# Schematic_v1.net
KiCad netlist of a schematic drawn in EAGLE
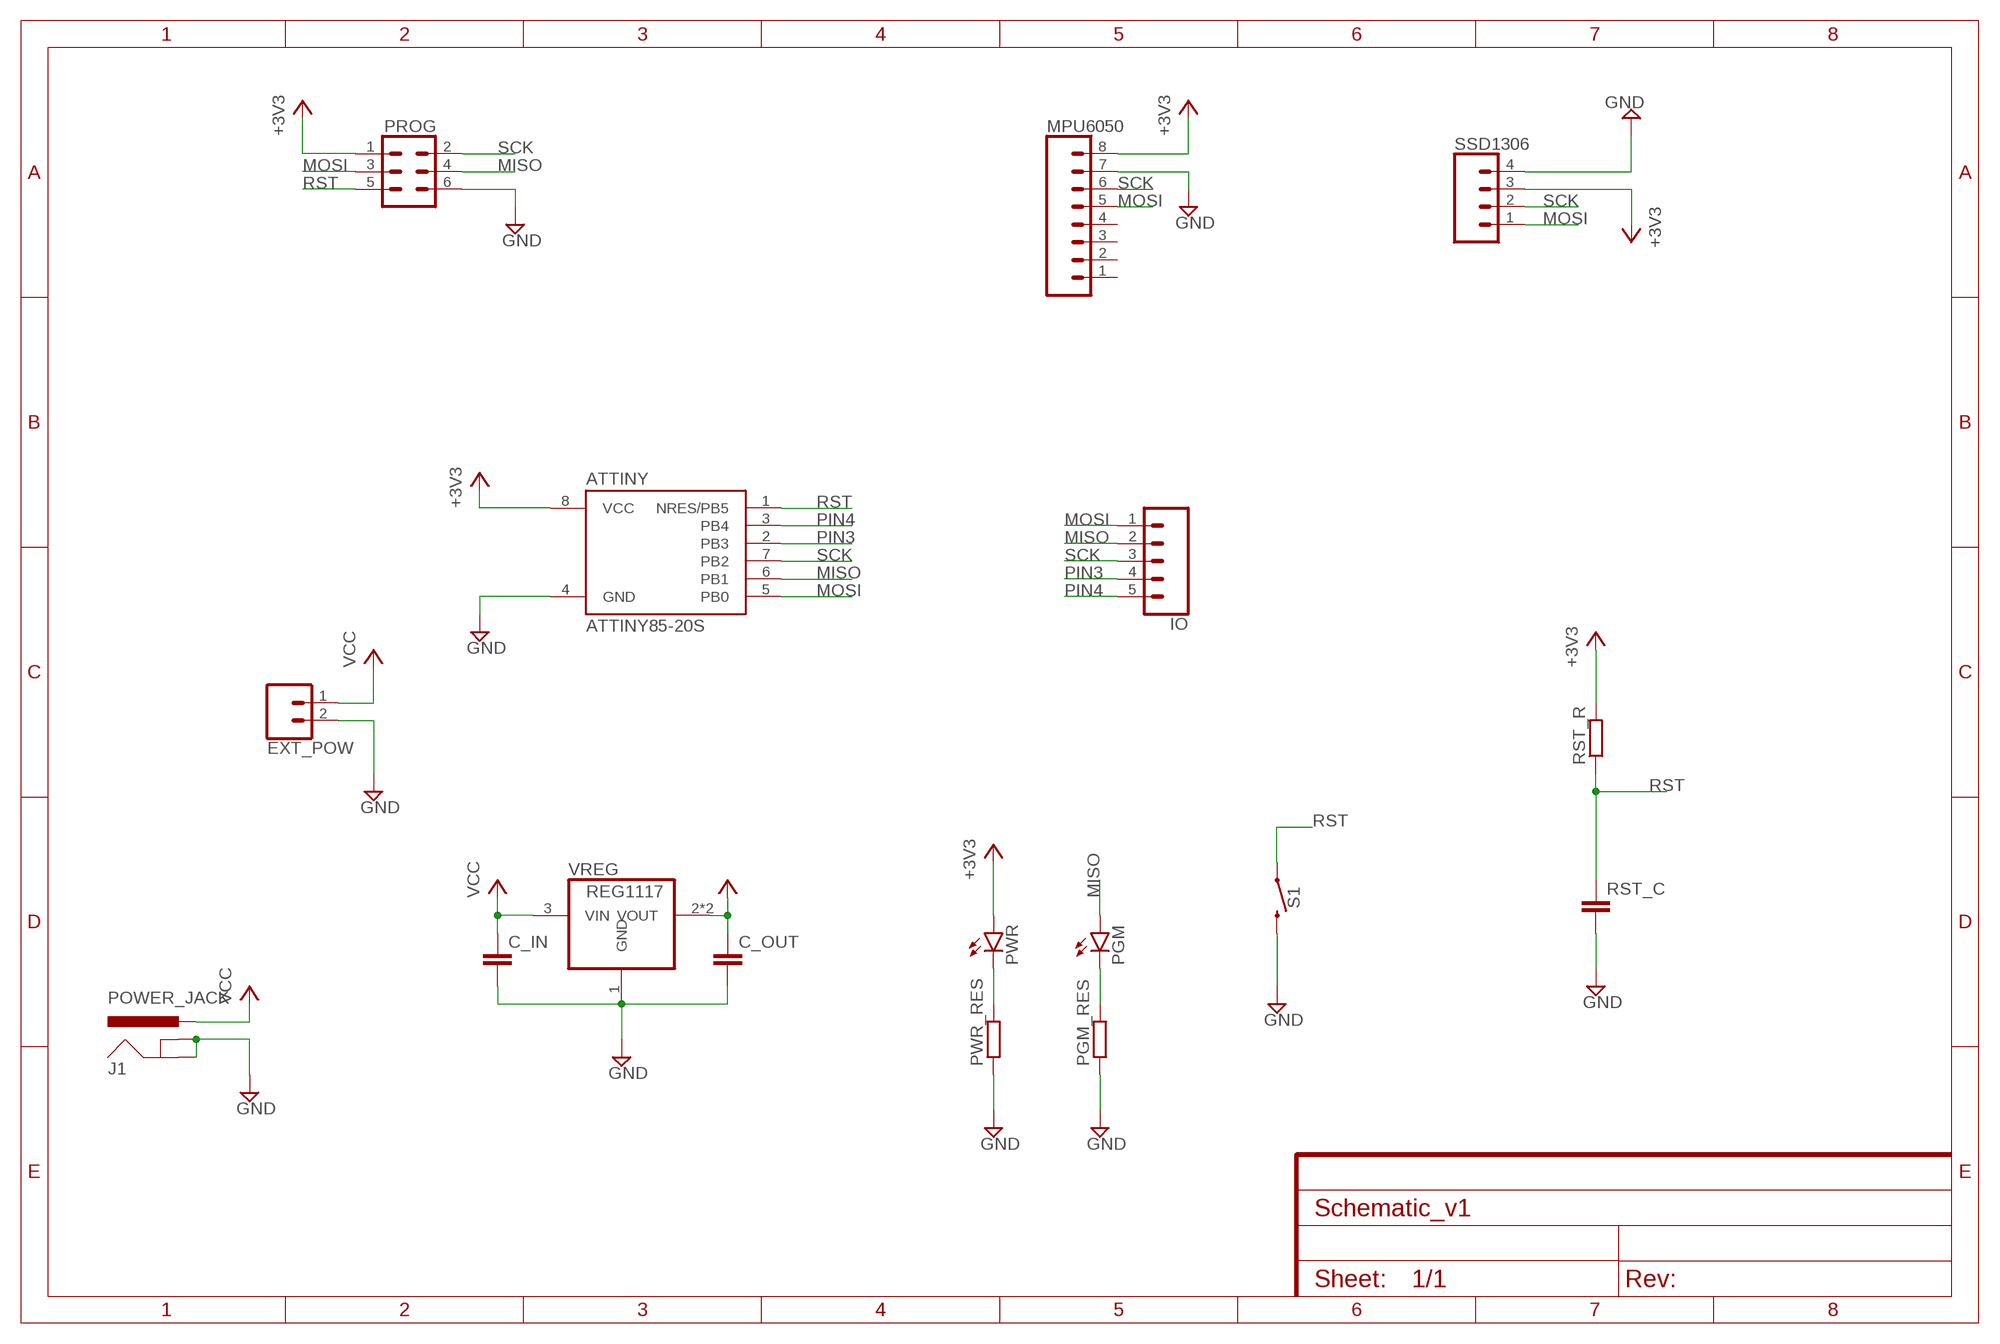
[diagram p0: schematic, sheet 1]

(export (version "E")
  (design (tool "Eeschema 10.0.6"))
  (components
    (comp (ref "ATTINY")
      (value "ATTINY85-20S")
      (footprint "eagle-import:SOIC8_EIAJ_208MIL")
      (libsource (lib "eagle-import") (part "ATTINY85S-20"))
    )
    (comp (ref "C_IN")
      (value "C-EUC1206")
      (footprint "eagle-import:C1206")
      (libsource (lib "eagle-import") (part "C-EUC1206"))
    )
    (comp (ref "C_OUT")
      (value "C-EUC1206")
      (footprint "eagle-import:C1206")
      (libsource (lib "eagle-import") (part "C-EUC1206"))
    )
    (comp (ref "EXT_POW")
      (value "CONN_021X02_NO_SILK")
      (footprint "eagle-import:1X02_NO_SILK")
      (libsource (lib "eagle-import") (part "CONN_021X02_NO_SILK"))
    )
    (comp (ref "IO")
      (value "CONN_05")
      (footprint "eagle-import:1X05")
      (libsource (lib "eagle-import") (part "CONN_05"))
    )
    (comp (ref "J1")
      (value "POWER_JACK")
      (footprint "eagle-import:POWER_JACK_PTH")
      (libsource (lib "eagle-import") (part "POWER_JACK"))
    )
    (comp (ref "MPU6050")
      (value "CONN_08\"")
      (footprint "eagle-import:1X08")
      (libsource (lib "eagle-import") (part "CONN_08{dblquote}"))
    )
    (comp (ref "PGM")
      (value "LEDSML1206")
      (footprint "eagle-import:SML1206")
      (libsource (lib "eagle-import") (part "LEDSML1206"))
    )
    (comp (ref "PGM_RES")
      (value "R-EU_R1206")
      (footprint "eagle-import:R1206")
      (libsource (lib "eagle-import") (part "R-EU_R1206"))
    )
    (comp (ref "PROG")
      (value "CONN_03X2NO_SILK")
      (footprint "eagle-import:2X3-NS")
      (libsource (lib "eagle-import") (part "CONN_03X2NO_SILK"))
    )
    (comp (ref "PWR")
      (value "LEDSML1206")
      (footprint "eagle-import:SML1206")
      (libsource (lib "eagle-import") (part "LEDSML1206"))
    )
    (comp (ref "PWR_RES")
      (value "R-EU_R1206")
      (footprint "eagle-import:R1206")
      (libsource (lib "eagle-import") (part "R-EU_R1206"))
    )
    (comp (ref "RST_C")
      (value "C-EUC1206")
      (footprint "eagle-import:C1206")
      (libsource (lib "eagle-import") (part "C-EUC1206"))
    )
    (comp (ref "RST_R")
      (value "R-EU_R1206")
      (footprint "eagle-import:R1206")
      (libsource (lib "eagle-import") (part "R-EU_R1206"))
    )
    (comp (ref "S1")
      (value "MOMENTARY-SWITCH-SPST-PTH-6.0MM")
      (footprint "eagle-import:TACTILE_SWITCH_PTH_6.0MM")
      (libsource (lib "eagle-import") (part "MOMENTARY-SWITCH-SPST-PTH-6.0MM"))
    )
    (comp (ref "SSD1306")
      (value "CONN_04")
      (footprint "eagle-import:1X04")
      (libsource (lib "eagle-import") (part "CONN_04"))
    )
    (comp (ref "VREG")
      (value "REG1117")
      (footprint "eagle-import:SOT223")
      (libsource (lib "eagle-import") (part "REG1117"))
    )
  )
  (nets
    (net (code "1") (name "+3V3") (class "Default")
      (node (ref "ATTINY") (pin "8") (pinfunction "VCC_8") (pintype "power_in"))
      (node (ref "C_OUT") (pin "1") (pinfunction "1_1") (pintype "passive"))
      (node (ref "MPU6050") (pin "8") (pinfunction "8_8") (pintype "passive"))
      (node (ref "PROG") (pin "1") (pinfunction "1_1") (pintype "bidirectional"))
      (node (ref "PWR") (pin "A") (pinfunction "A_A") (pintype "passive"))
      (node (ref "RST_R") (pin "2") (pinfunction "2_2") (pintype "passive"))
      (node (ref "SSD1306") (pin "3") (pinfunction "3_3") (pintype "passive"))
      (node (ref "VREG") (pin "2") (pinfunction "VOUT_2") (pintype "output"))
      (node (ref "VREG") (pin "4") (pinfunction "VOUT_4") (pintype "output"))
    )
    (net (code "2") (name "/MISO") (class "Default")
      (node (ref "ATTINY") (pin "6") (pinfunction "PB1_6") (pintype "bidirectional"))
      (node (ref "IO") (pin "2") (pinfunction "2_2") (pintype "passive"))
      (node (ref "PGM") (pin "A") (pinfunction "A_A") (pintype "passive"))
      (node (ref "PROG") (pin "4") (pinfunction "4_4") (pintype "bidirectional"))
    )
    (net (code "3") (name "/MOSI") (class "Default")
      (node (ref "ATTINY") (pin "5") (pinfunction "PB0_5") (pintype "bidirectional"))
      (node (ref "IO") (pin "1") (pinfunction "1_1") (pintype "passive"))
      (node (ref "MPU6050") (pin "5") (pinfunction "5_5") (pintype "passive"))
      (node (ref "PROG") (pin "3") (pinfunction "3_3") (pintype "bidirectional"))
      (node (ref "SSD1306") (pin "1") (pinfunction "1_1") (pintype "passive"))
    )
    (net (code "4") (name "/PIN3") (class "Default")
      (node (ref "ATTINY") (pin "2") (pinfunction "PB3_2") (pintype "bidirectional"))
      (node (ref "IO") (pin "4") (pinfunction "4_4") (pintype "passive"))
    )
    (net (code "5") (name "/PIN4") (class "Default")
      (node (ref "ATTINY") (pin "3") (pinfunction "PB4_3") (pintype "bidirectional"))
      (node (ref "IO") (pin "5") (pinfunction "5_5") (pintype "passive"))
    )
    (net (code "6") (name "/RST") (class "Default")
      (node (ref "ATTINY") (pin "1") (pinfunction "NRES/PB5_1") (pintype "bidirectional"))
      (node (ref "PROG") (pin "5") (pinfunction "5_5") (pintype "bidirectional"))
      (node (ref "RST_C") (pin "1") (pinfunction "1_1") (pintype "passive"))
      (node (ref "RST_R") (pin "1") (pinfunction "1_1") (pintype "passive"))
      (node (ref "S1") (pin "1") (pinfunction "1_1") (pintype "passive"))
    )
    (net (code "7") (name "/SCK") (class "Default")
      (node (ref "ATTINY") (pin "7") (pinfunction "PB2_7") (pintype "bidirectional"))
      (node (ref "IO") (pin "3") (pinfunction "3_3") (pintype "passive"))
      (node (ref "MPU6050") (pin "6") (pinfunction "6_6") (pintype "passive"))
      (node (ref "PROG") (pin "2") (pinfunction "2_2") (pintype "bidirectional"))
      (node (ref "SSD1306") (pin "2") (pinfunction "2_2") (pintype "passive"))
    )
    (net (code "8") (name "GND") (class "Default")
      (node (ref "ATTINY") (pin "4") (pinfunction "GND_4") (pintype "power_in"))
      (node (ref "C_IN") (pin "2") (pinfunction "2_2") (pintype "passive"))
      (node (ref "C_OUT") (pin "2") (pinfunction "2_2") (pintype "passive"))
      (node (ref "EXT_POW") (pin "2") (pinfunction "2_2") (pintype "passive"))
      (node (ref "J1") (pin "GND") (pinfunction "GND_GND") (pintype "bidirectional"))
      (node (ref "J1") (pin "GNDBREAK") (pinfunction "GNDBREAK_GNDBREAK") (pintype "bidirectional"))
      (node (ref "MPU6050") (pin "7") (pinfunction "7_7") (pintype "passive"))
      (node (ref "PGM_RES") (pin "1") (pinfunction "1_1") (pintype "passive"))
      (node (ref "PROG") (pin "6") (pinfunction "6_6") (pintype "bidirectional"))
      (node (ref "PWR_RES") (pin "1") (pinfunction "1_1") (pintype "passive"))
      (node (ref "RST_C") (pin "2") (pinfunction "2_2") (pintype "passive"))
      (node (ref "S1") (pin "3") (pinfunction "2_3") (pintype "passive"))
      (node (ref "SSD1306") (pin "4") (pinfunction "4_4") (pintype "passive"))
      (node (ref "VREG") (pin "1") (pinfunction "GND_1") (pintype "power_in"))
    )
    (net (code "9") (name "Net-(PGM-PadC)") (class "Default")
      (node (ref "PGM") (pin "C") (pinfunction "C_C") (pintype "passive"))
      (node (ref "PGM_RES") (pin "2") (pinfunction "2_2") (pintype "passive"))
    )
    (net (code "10") (name "Net-(PWR-PadC)") (class "Default")
      (node (ref "PWR") (pin "C") (pinfunction "C_C") (pintype "passive"))
      (node (ref "PWR_RES") (pin "2") (pinfunction "2_2") (pintype "passive"))
    )
    (net (code "11") (name "VCC") (class "Default")
      (node (ref "C_IN") (pin "1") (pinfunction "1_1") (pintype "passive"))
      (node (ref "EXT_POW") (pin "1") (pinfunction "1_1") (pintype "passive"))
      (node (ref "J1") (pin "PWR") (pinfunction "PWR_PWR") (pintype "bidirectional"))
      (node (ref "VREG") (pin "3") (pinfunction "VIN_3") (pintype "input"))
    )
    (net (code "12") (name "unconnected-(MPU6050-Pad1)") (class "Default")
      (node (ref "MPU6050") (pin "1") (pinfunction "1_1") (pintype "passive"))
    )
    (net (code "13") (name "unconnected-(MPU6050-Pad2)") (class "Default")
      (node (ref "MPU6050") (pin "2") (pinfunction "2_2") (pintype "passive"))
    )
    (net (code "14") (name "unconnected-(MPU6050-Pad3)") (class "Default")
      (node (ref "MPU6050") (pin "3") (pinfunction "3_3") (pintype "passive"))
    )
    (net (code "15") (name "unconnected-(MPU6050-Pad4)") (class "Default")
      (node (ref "MPU6050") (pin "4") (pinfunction "4_4") (pintype "passive"))
    )
  )
)
